# 13-ESP32S3.net
KiCad netlist of a schematic drawn in Altium Designer
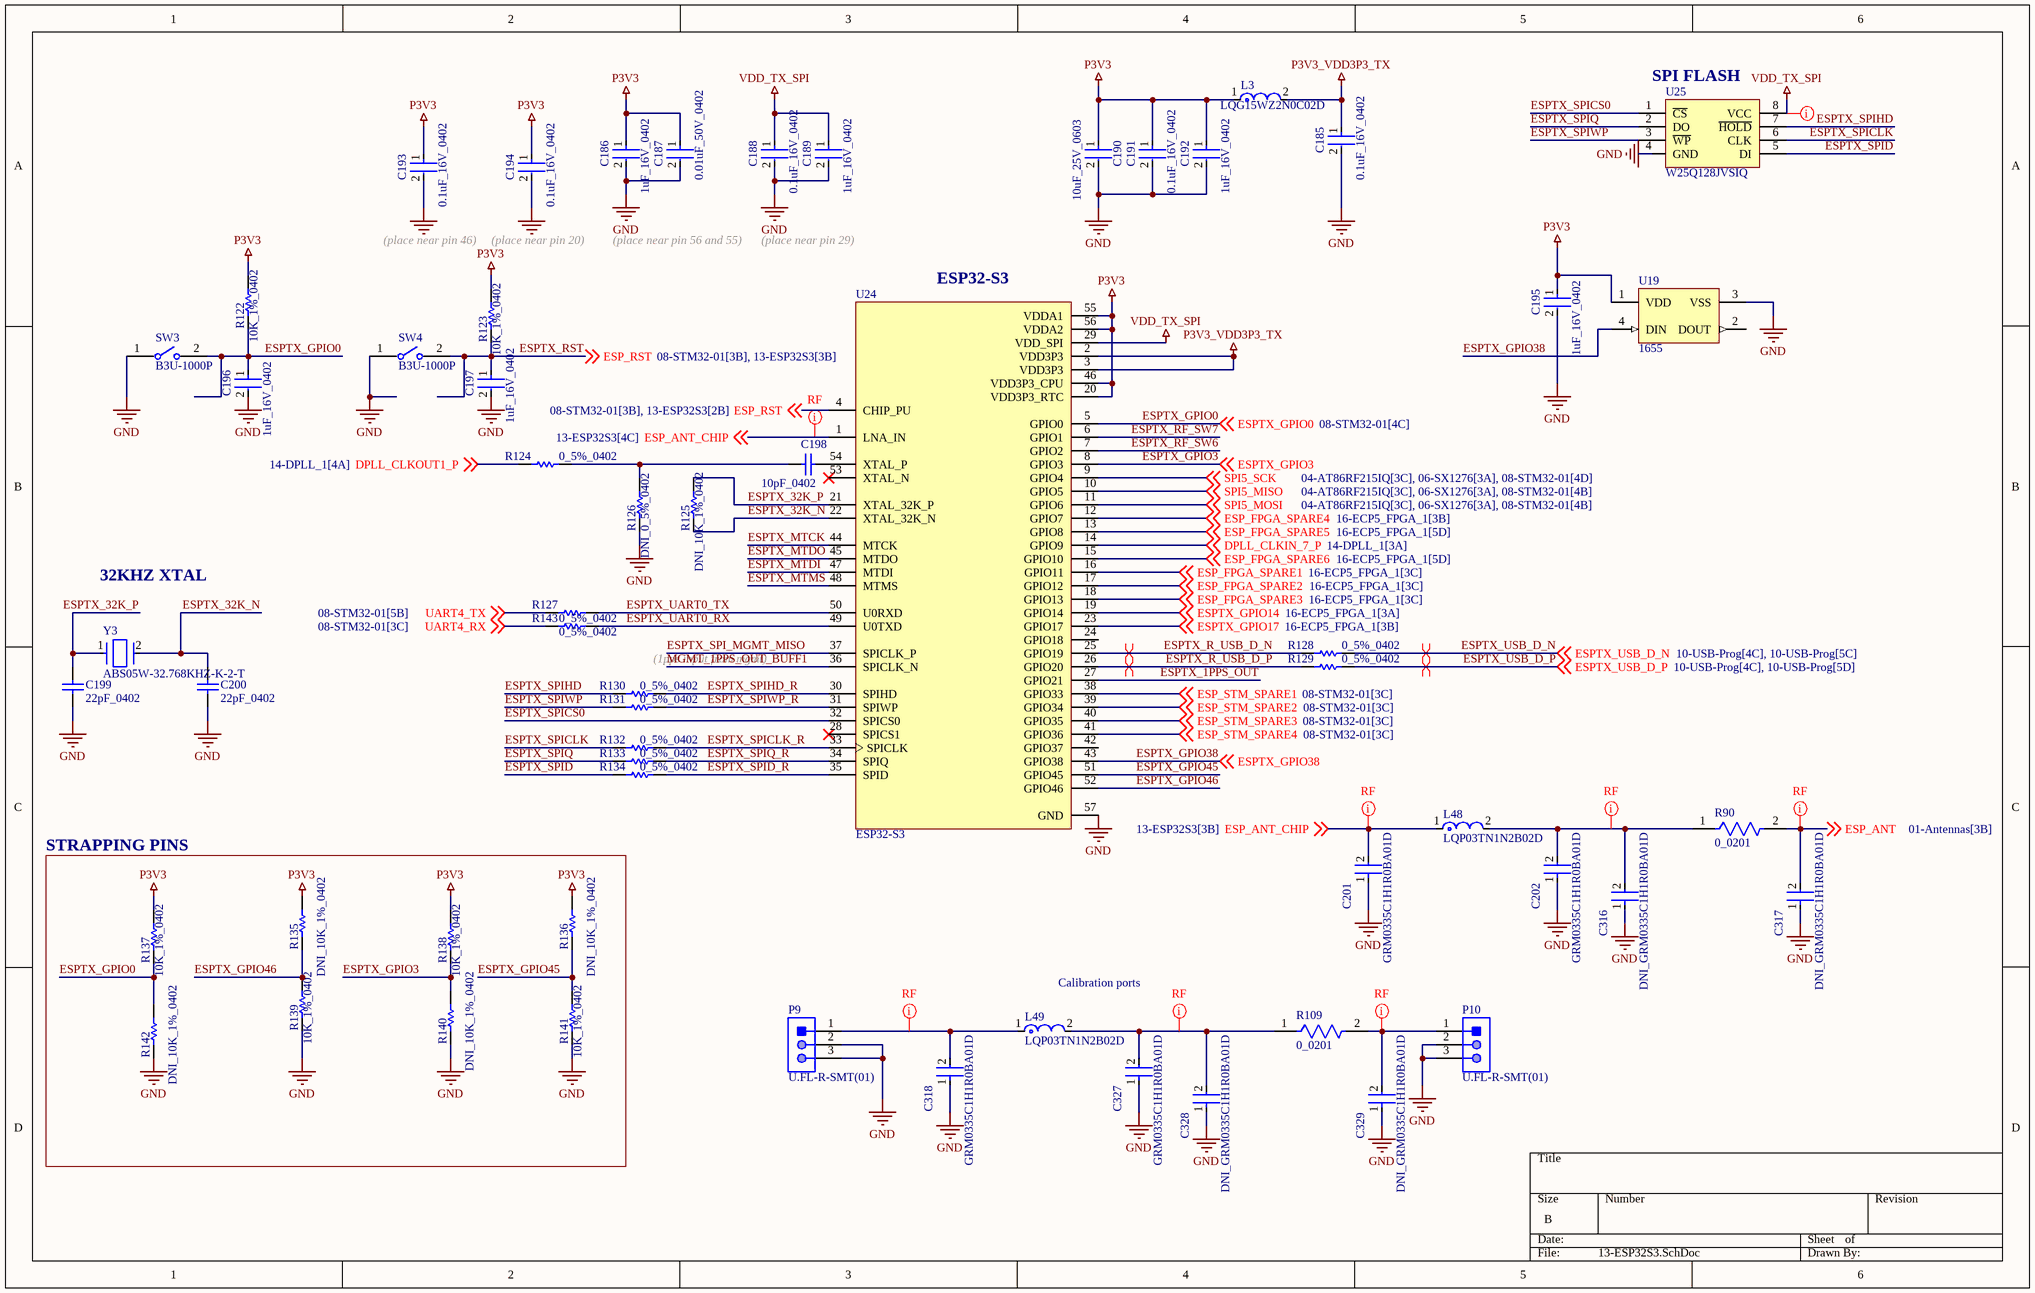
[diagram p0: 13-ESP32S3.SchDoc]

(export (version "E")
  (design (tool "Eeschema 10.0.6"))
  (components
    (comp (ref "C185")
      (value "0.1uF_16V_0402")
      (footprint "FP-C0402-BB-MFG")
      (description "CAP CER 0.1UF 16V 5% X7R 0402")
      (fields
        (field (name "MANUFACTURER") "Kemet")
        (field (name "MANUFACTURER PART NUMBER") "C0402C104J4RACTU")
      )
      (libsource (lib "Altium Content Vault") (part "b4654b650e69147ec39a6b967a45e02"))
    )
    (comp (ref "C186")
      (value "1uF_16V_0402")
      (footprint "FP-0402-L_1_0_0_05-W_0_5-IPC_A")
      (description "None")
      (fields (field (name "TOLERANCE") "10%"))
      (libsource (lib "Altium Content Vault") (part "b4654b650e69147ec39a6b967a45e02"))
    )
    (comp (ref "C187")
      (value "0.01uF_50V_0402")
      (footprint "FP-GCM155-0_05-IPC_C")
      (description "Ceramic Capacitor for Automotive 10nF ±10% 50VDC X7R 0402 Paper T/R")
      (fields (field (name "TOLERANCE") "10%") (field (name "VOLTAGE") "50V"))
      (libsource (lib "Altium Content Vault") (part "02cd4be3c70576c341d710602a673aa"))
    )
    (comp (ref "C188")
      (value "0.1uF_16V_0402")
      (footprint "FP-C0402-BB-MFG")
      (description "CAP CER 0.1UF 16V 5% X7R 0402")
      (fields
        (field (name "MANUFACTURER") "Kemet")
        (field (name "MANUFACTURER PART NUMBER") "C0402C104J4RACTU")
      )
      (libsource (lib "Altium Content Vault") (part "b4654b650e69147ec39a6b967a45e02"))
    )
    (comp (ref "C189")
      (value "1uF_16V_0402")
      (footprint "FP-0402-L_1_0_0_05-W_0_5-IPC_A")
      (description "None")
      (fields (field (name "TOLERANCE") "10%"))
      (libsource (lib "Altium Content Vault") (part "b4654b650e69147ec39a6b967a45e02"))
    )
    (comp (ref "C190")
      (value "10uF_25V_0603")
      (footprint "FP-CL10-IPC_C")
      (description "Cap Ceramic 10uF 25V X5R ±20% Pad SMD 0603 +85°C T/R")
      (fields (field (name "TOLERANCE") "20%"))
      (libsource (lib "Altium Content Vault") (part "b4654b650e69147ec39a6b967a45e02"))
    )
    (comp (ref "C191")
      (value "0.1uF_16V_0402")
      (footprint "FP-C0402-BB-MFG")
      (description "CAP CER 0.1UF 16V 5% X7R 0402")
      (fields
        (field (name "MANUFACTURER") "Kemet")
        (field (name "MANUFACTURER PART NUMBER") "C0402C104J4RACTU")
      )
      (libsource (lib "Altium Content Vault") (part "b4654b650e69147ec39a6b967a45e02"))
    )
    (comp (ref "C192")
      (value "1uF_16V_0402")
      (footprint "FP-0402-L_1_0_0_05-W_0_5-IPC_A")
      (description "None")
      (fields (field (name "TOLERANCE") "10%"))
      (libsource (lib "Altium Content Vault") (part "b4654b650e69147ec39a6b967a45e02"))
    )
    (comp (ref "C193")
      (value "0.1uF_16V_0402")
      (footprint "FP-C0402-BB-MFG")
      (description "CAP CER 0.1UF 16V 5% X7R 0402")
      (fields
        (field (name "MANUFACTURER") "Kemet")
        (field (name "MANUFACTURER PART NUMBER") "C0402C104J4RACTU")
      )
      (libsource (lib "Altium Content Vault") (part "b4654b650e69147ec39a6b967a45e02"))
    )
    (comp (ref "C194")
      (value "0.1uF_16V_0402")
      (footprint "FP-C0402-BB-MFG")
      (description "CAP CER 0.1UF 16V 5% X7R 0402")
      (fields
        (field (name "MANUFACTURER") "Kemet")
        (field (name "MANUFACTURER PART NUMBER") "C0402C104J4RACTU")
      )
      (libsource (lib "Altium Content Vault") (part "b4654b650e69147ec39a6b967a45e02"))
    )
    (comp (ref "C195")
      (value "1uF_16V_0402")
      (footprint "FP-0402-L_1_0_0_05-W_0_5-IPC_A")
      (description "None")
      (fields (field (name "TOLERANCE") "10%"))
      (libsource (lib "Altium Content Vault") (part "b4654b650e69147ec39a6b967a45e02"))
    )
    (comp (ref "C196")
      (value "1uF_16V_0402")
      (footprint "FP-0402-L_1_0_0_05-W_0_5-IPC_A")
      (description "None")
      (fields (field (name "TOLERANCE") "10%"))
      (libsource (lib "Altium Content Vault") (part "b4654b650e69147ec39a6b967a45e02"))
    )
    (comp (ref "C197")
      (value "1uF_16V_0402")
      (footprint "FP-0402-L_1_0_0_05-W_0_5-IPC_A")
      (description "None")
      (fields (field (name "TOLERANCE") "10%"))
      (libsource (lib "Altium Content Vault") (part "b4654b650e69147ec39a6b967a45e02"))
    )
    (comp (ref "C198")
      (value "10pF_0402")
      (footprint "CAPC1005X55X25ML05T05")
      (description "Chip Capacitor, 10 pF, +/- 5%, 50 V, -55 to 125 degC, 0402 (1005 Metric), RoHS, Tape and Reel")
      (fields (field (name "TOLERANCE") "5%") (field (name "MANUFACTURER") "Yageo"))
      (libsource (lib "Altium Content Vault") (part "CAP-NP-2"))
    )
    (comp (ref "C199")
      (value "22pF_0402")
      (footprint "CAPC1005X55X25ML05T05")
      (description "Chip Capacitor, 22 pF, +/- 5%, 50 V, -55 to 125 degC, 0402 (1005 Metric), RoHS, Tape and Reel")
      (fields (field (name "MANUFACTURER") "Yageo") (field (name "TOLERANCE") "5%"))
      (libsource (lib "Altium Content Vault") (part "CAP-NP-2"))
    )
    (comp (ref "C200")
      (value "22pF_0402")
      (footprint "CAPC1005X55X25ML05T05")
      (description "Chip Capacitor, 22 pF, +/- 5%, 50 V, -55 to 125 degC, 0402 (1005 Metric), RoHS, Tape and Reel")
      (fields (field (name "MANUFACTURER") "Yageo") (field (name "TOLERANCE") "5%"))
      (libsource (lib "Altium Content Vault") (part "CAP-NP-2"))
    )
    (comp (ref "C201")
      (value "GRM0335C1H1R0BA01D")
      (footprint "FP-GRM033-0_03-IPC_C")
      (description "Chip Multilayer Ceramic Capacitors for General Purpose, 0201, 1.0pF, C0G, 30ppm/°C, 0.1pF, 50V")
      (libsource (lib "Altium Content Vault") (part "b4654b650e69147ec39a6b967a45e02"))
    )
    (comp (ref "C202")
      (value "GRM0335C1H1R0BA01D")
      (footprint "FP-GRM033-0_03-IPC_C")
      (description "Chip Multilayer Ceramic Capacitors for General Purpose, 0201, 1.0pF, C0G, 30ppm/°C, 0.1pF, 50V")
      (libsource (lib "Altium Content Vault") (part "b4654b650e69147ec39a6b967a45e02"))
    )
    (comp (ref "C316")
      (value "DNI_GRM0335C1H1R0BA01D")
      (footprint "FP-GRM033-0_03-IPC_C")
      (description "Chip Multilayer Ceramic Capacitors for General Purpose, 0201, 1.0pF, C0G, 30ppm/°C, 0.1pF, 50V")
      (libsource (lib "Altium Content Vault") (part "b4654b650e69147ec39a6b967a45e02"))
    )
    (comp (ref "C317")
      (value "DNI_GRM0335C1H1R0BA01D")
      (footprint "FP-GRM033-0_03-IPC_C")
      (description "Chip Multilayer Ceramic Capacitors for General Purpose, 0201, 1.0pF, C0G, 30ppm/°C, 0.1pF, 50V")
      (libsource (lib "Altium Content Vault") (part "b4654b650e69147ec39a6b967a45e02"))
    )
    (comp (ref "C318")
      (value "GRM0335C1H1R0BA01D")
      (footprint "FP-GRM033-0_03-IPC_C")
      (description "Chip Multilayer Ceramic Capacitors for General Purpose, 0201, 1.0pF, C0G, 30ppm/°C, 0.1pF, 50V")
      (libsource (lib "Altium Content Vault") (part "b4654b650e69147ec39a6b967a45e02"))
    )
    (comp (ref "C327")
      (value "GRM0335C1H1R0BA01D")
      (footprint "FP-GRM033-0_03-IPC_C")
      (description "Chip Multilayer Ceramic Capacitors for General Purpose, 0201, 1.0pF, C0G, 30ppm/°C, 0.1pF, 50V")
      (libsource (lib "Altium Content Vault") (part "b4654b650e69147ec39a6b967a45e02"))
    )
    (comp (ref "C328")
      (value "DNI_GRM0335C1H1R0BA01D")
      (footprint "FP-GRM033-0_03-IPC_C")
      (description "Chip Multilayer Ceramic Capacitors for General Purpose, 0201, 1.0pF, C0G, 30ppm/°C, 0.1pF, 50V")
      (libsource (lib "Altium Content Vault") (part "b4654b650e69147ec39a6b967a45e02"))
    )
    (comp (ref "C329")
      (value "DNI_GRM0335C1H1R0BA01D")
      (footprint "FP-GRM033-0_03-IPC_C")
      (description "Chip Multilayer Ceramic Capacitors for General Purpose, 0201, 1.0pF, C0G, 30ppm/°C, 0.1pF, 50V")
      (libsource (lib "Altium Content Vault") (part "b4654b650e69147ec39a6b967a45e02"))
    )
    (comp (ref "L3")
      (value "LQG15WZ2N0C02D")
      (footprint "FP-LQG15WH_02-IPC_B")
      (description "Multilayer type Inductor for Automotive 2nH ±0.2nH 0.05Ω 1000mA 0402")
      (libsource (lib "Altium Content Vault") (part "4cc4b267dca4c8e51f7102f422741d8"))
    )
    (comp (ref "L48")
      (value "LQP03TN1N2B02D")
      (footprint "FP-LQP03TG_02-IPC_A")
      (description "Film type RF Inductor 1.2nH ±0.1nH 750mA 0.1Ω 0201 (0603)")
      (libsource (lib "Altium Content Vault") (part "4cc4b267dca4c8e51f7102f422741d8"))
    )
    (comp (ref "L49")
      (value "LQP03TN1N2B02D")
      (footprint "FP-LQP03TG_02-IPC_A")
      (description "Film type RF Inductor 1.2nH ±0.1nH 750mA 0.1Ω 0201 (0603)")
      (libsource (lib "Altium Content Vault") (part "4cc4b267dca4c8e51f7102f422741d8"))
    )
    (comp (ref "P9")
      (value "U.FL-R-SMT(01)")
      (footprint "HRS-U.FL-R-SMT(10)_V")
      (description "CONN RECPT ULTRA-MINI COAX SMD")
      (fields (field (name "MANUFACTURER") "Hirose Electric") (field (name "APPROVAL CATEGORY") "UL94V-0"))
      (libsource (lib "") (part "CN-1P-M-R3_1"))
    )
    (comp (ref "P10")
      (value "U.FL-R-SMT(01)")
      (footprint "HRS-U.FL-R-SMT(10)_V")
      (description "CONN RECPT ULTRA-MINI COAX SMD")
      (fields (field (name "MANUFACTURER") "Hirose Electric") (field (name "APPROVAL CATEGORY") "UL94V-0"))
      (libsource (lib "Altium Content Vault") (part "CN-1P-M-R3"))
    )
    (comp (ref "R90")
      (value "0_0201")
      (footprint "FP-RC_L0201-MFG")
      (description "RES SMD 0 OHM JUMPER 1/20W 0201")
      (fields
        (field (name "OCTOPART") "https://octopart.com/rc0201jr-070rl-yageo-43171986")
        (field (name "MANUFACTURER") "Yageo")
      )
      (libsource (lib "Altium Content Vault") (part "1029c3af85768c4190bb7ad29bc67b5"))
    )
    (comp (ref "R109")
      (value "0_0201")
      (footprint "FP-RC_L0201-MFG")
      (description "RES SMD 0 OHM JUMPER 1/20W 0201")
      (fields
        (field (name "OCTOPART") "https://octopart.com/rc0201jr-070rl-yageo-43171986")
        (field (name "MANUFACTURER") "Yageo")
      )
      (libsource (lib "Altium Content Vault") (part "1029c3af85768c4190bb7ad29bc67b5"))
    )
    (comp (ref "R122")
      (value "10K_1%_0402")
      (footprint "RESC1005X40X25NL10T10")
      (fields (field (name "MANUFACTURER") "Bourns") (field (name "PART NUMBER") "CR0402-FX-1002GLF"))
      (libsource (lib "Altium Content Vault") (part "RES"))
    )
    (comp (ref "R123")
      (value "10K_1%_0402")
      (footprint "RESC1005X40X25NL10T10")
      (fields (field (name "MANUFACTURER") "Bourns") (field (name "PART NUMBER") "CR0402-FX-1002GLF"))
      (libsource (lib "Altium Content Vault") (part "RES"))
    )
    (comp (ref "R124")
      (value "0_5%_0402")
      (footprint "RESC1005X40X25NL05T10")
      (fields (field (name "MANUFACTURER") "Panasonic") (field (name "PART NUMBER") "ERJ-U020R00X"))
      (libsource (lib "Altium Content Vault") (part "RES"))
    )
    (comp (ref "R125")
      (value "DNI_10K_1%_0402")
      (footprint "RESC1005X40X25NL10T10")
      (fields (field (name "MANUFACTURER") "Bourns") (field (name "PART NUMBER") "CR0402-FX-1002GLF"))
      (libsource (lib "Altium Content Vault") (part "RES"))
    )
    (comp (ref "R126")
      (value "DNI_0_5%_0402")
      (footprint "RESC1005X40X25NL05T10")
      (fields (field (name "MANUFACTURER") "Panasonic") (field (name "PART NUMBER") "ERJ-U020R00X"))
      (libsource (lib "Altium Content Vault") (part "RES"))
    )
    (comp (ref "R127")
      (value "0_5%_0402")
      (footprint "RESC1005X40X25NL05T10")
      (fields (field (name "MANUFACTURER") "Panasonic") (field (name "PART NUMBER") "ERJ-U020R00X"))
      (libsource (lib "Altium Content Vault") (part "RES"))
    )
    (comp (ref "R128")
      (value "0_5%_0402")
      (footprint "RESC1005X40X25NL05T10")
      (fields (field (name "MANUFACTURER") "Panasonic") (field (name "PART NUMBER") "ERJ-U020R00X"))
      (libsource (lib "Altium Content Vault") (part "RES"))
    )
    (comp (ref "R129")
      (value "0_5%_0402")
      (footprint "RESC1005X40X25NL05T10")
      (fields (field (name "MANUFACTURER") "Panasonic") (field (name "PART NUMBER") "ERJ-U020R00X"))
      (libsource (lib "Altium Content Vault") (part "RES"))
    )
    (comp (ref "R130")
      (value "0_5%_0402")
      (footprint "RESC1005X40X25NL05T10")
      (fields (field (name "MANUFACTURER") "Panasonic") (field (name "PART NUMBER") "ERJ-U020R00X"))
      (libsource (lib "Altium Content Vault") (part "RES"))
    )
    (comp (ref "R131")
      (value "0_5%_0402")
      (footprint "RESC1005X40X25NL05T10")
      (fields (field (name "MANUFACTURER") "Panasonic") (field (name "PART NUMBER") "ERJ-U020R00X"))
      (libsource (lib "Altium Content Vault") (part "RES"))
    )
    (comp (ref "R132")
      (value "0_5%_0402")
      (footprint "RESC1005X40X25NL05T10")
      (fields (field (name "MANUFACTURER") "Panasonic") (field (name "PART NUMBER") "ERJ-U020R00X"))
      (libsource (lib "Altium Content Vault") (part "RES"))
    )
    (comp (ref "R133")
      (value "0_5%_0402")
      (footprint "RESC1005X40X25NL05T10")
      (fields (field (name "MANUFACTURER") "Panasonic") (field (name "PART NUMBER") "ERJ-U020R00X"))
      (libsource (lib "Altium Content Vault") (part "RES"))
    )
    (comp (ref "R134")
      (value "0_5%_0402")
      (footprint "RESC1005X40X25NL05T10")
      (fields (field (name "MANUFACTURER") "Panasonic") (field (name "PART NUMBER") "ERJ-U020R00X"))
      (libsource (lib "Altium Content Vault") (part "RES"))
    )
    (comp (ref "R135")
      (value "DNI_10K_1%_0402")
      (footprint "RESC1005X40X25NL10T10")
      (fields (field (name "MANUFACTURER") "Bourns") (field (name "PART NUMBER") "CR0402-FX-1002GLF"))
      (libsource (lib "Altium Content Vault") (part "RES"))
    )
    (comp (ref "R136")
      (value "DNI_10K_1%_0402")
      (footprint "RESC1005X40X25NL10T10")
      (fields (field (name "MANUFACTURER") "Bourns") (field (name "PART NUMBER") "CR0402-FX-1002GLF"))
      (libsource (lib "Altium Content Vault") (part "RES"))
    )
    (comp (ref "R137")
      (value "10K_1%_0402")
      (footprint "RESC1005X40X25NL10T10")
      (fields (field (name "MANUFACTURER") "Bourns") (field (name "PART NUMBER") "CR0402-FX-1002GLF"))
      (libsource (lib "Altium Content Vault") (part "RES"))
    )
    (comp (ref "R138")
      (value "10K_1%_0402")
      (footprint "RESC1005X40X25NL10T10")
      (fields (field (name "MANUFACTURER") "Bourns") (field (name "PART NUMBER") "CR0402-FX-1002GLF"))
      (libsource (lib "Altium Content Vault") (part "RES"))
    )
    (comp (ref "R139")
      (value "10K_1%_0402")
      (footprint "RESC1005X40X25NL10T10")
      (fields (field (name "MANUFACTURER") "Bourns") (field (name "PART NUMBER") "CR0402-FX-1002GLF"))
      (libsource (lib "Altium Content Vault") (part "RES"))
    )
    (comp (ref "R140")
      (value "DNI_10K_1%_0402")
      (footprint "RESC1005X40X25NL10T10")
      (fields (field (name "MANUFACTURER") "Bourns") (field (name "PART NUMBER") "CR0402-FX-1002GLF"))
      (libsource (lib "Altium Content Vault") (part "RES"))
    )
    (comp (ref "R141")
      (value "10K_1%_0402")
      (footprint "RESC1005X40X25NL10T10")
      (fields (field (name "MANUFACTURER") "Bourns") (field (name "PART NUMBER") "CR0402-FX-1002GLF"))
      (libsource (lib "Altium Content Vault") (part "RES"))
    )
    (comp (ref "R142")
      (value "DNI_10K_1%_0402")
      (footprint "RESC1005X40X25NL10T10")
      (fields (field (name "MANUFACTURER") "Bourns") (field (name "PART NUMBER") "CR0402-FX-1002GLF"))
      (libsource (lib "Altium Content Vault") (part "RES"))
    )
    (comp (ref "R143")
      (value "0_5%_0402")
      (footprint "RESC1005X40X25NL05T10")
      (fields (field (name "MANUFACTURER") "Panasonic") (field (name "PART NUMBER") "ERJ-U020R00X"))
      (libsource (lib "Altium Content Vault") (part "RES"))
    )
    (comp (ref "SW3")
      (value "B3U-1000P")
      (footprint "FP-B3U-1000P-MFG")
      (description "SWITCH TACTILE SPST-NO 0.05A 12V")
      (libsource (lib "Altium Content Vault") (part "ae622034201233ca1abcedc05908f33"))
    )
    (comp (ref "SW4")
      (value "B3U-1000P")
      (footprint "FP-B3U-1000P-MFG")
      (description "SWITCH TACTILE SPST-NO 0.05A 12V")
      (libsource (lib "Altium Content Vault") (part "ae622034201233ca1abcedc05908f33"))
    )
    (comp (ref "U19")
      (value "1655")
      (footprint "ADA-RGB-1655_V")
      (fields (field (name "MANUFACTURER") "Adafruit-Industries-LLC"))
      (libsource (lib "Altium Content Vault") (part "ADA-RGB-1655-4"))
    )
    (comp (ref "U24")
      (value "ESP32-S3")
      (footprint "IC_ESP32-S3")
      (fields (field (name "MF") "Espressif Systems"))
      (libsource (lib "LotusSound") (part "IC_ESP32-S3"))
    )
    (comp (ref "U25")
      (value "W25Q128JVSIQ")
      (footprint "IC_W25Q128JVSIQ")
      (description "NOR Flash Serial (SPI, Dual SPI, Quad SPI) 3.3V 128M-bit 16M x 8 6ns 8-Pin SOIC Tube")
      (fields (field (name "MANUFACTURER") "Winbond"))
      (libsource (lib "LotusSound") (part "IC_W25Q128JVSIQ"))
    )
    (comp (ref "Y3")
      (value "ABS05W-32.768KHZ-K-2-T")
      (footprint "FP-ABS05W-MFG")
      (description "Crystal 32.768kHz ±20ppm (Tol) 4pF 85kΩ 2-Pin SMD T/R")
      (libsource (lib "Altium Content Vault") (part "c23a69dc6c9e2f18f2079038eb95dd1"))
    )
  )
  (nets
    (net (code "1") (name "/ESPTX_1PPS_OUT") (class "Default")
      (node (ref "U24") (pin "27") (pinfunction "GPIO21_27") (pintype "passive"))
    )
    (net (code "2") (name "/ESPTX_32K_N") (class "Default")
      (node (ref "C200") (pin "2") (pinfunction "2_2") (pintype "passive"))
      (node (ref "R125") (pin "1") (pinfunction "1_1") (pintype "passive"))
      (node (ref "U24") (pin "22") (pinfunction "XTAL_32K_N_22") (pintype "passive"))
      (node (ref "Y3") (pin "2") (pinfunction "2_2") (pintype "passive"))
    )
    (net (code "3") (name "/ESPTX_32K_P") (class "Default")
      (node (ref "C199") (pin "2") (pinfunction "2_2") (pintype "passive"))
      (node (ref "R125") (pin "2") (pinfunction "2_2") (pintype "passive"))
      (node (ref "U24") (pin "21") (pinfunction "XTAL_32K_P_21") (pintype "passive"))
      (node (ref "Y3") (pin "1") (pinfunction "1_1") (pintype "passive"))
    )
    (net (code "4") (name "/ESPTX_GPIO45") (class "Default")
      (node (ref "R136") (pin "1") (pinfunction "1_1") (pintype "passive"))
      (node (ref "R141") (pin "2") (pinfunction "2_2") (pintype "passive"))
      (node (ref "U24") (pin "51") (pinfunction "GPIO45_51") (pintype "passive"))
    )
    (net (code "5") (name "/ESPTX_GPIO46") (class "Default")
      (node (ref "R135") (pin "1") (pinfunction "1_1") (pintype "passive"))
      (node (ref "R139") (pin "2") (pinfunction "2_2") (pintype "passive"))
      (node (ref "U24") (pin "52") (pinfunction "GPIO46_52") (pintype "passive"))
    )
    (net (code "6") (name "/ESPTX_MTCK") (class "Default")
      (node (ref "U24") (pin "44") (pinfunction "MTCK_44") (pintype "passive"))
    )
    (net (code "7") (name "/ESPTX_MTDI") (class "Default")
      (node (ref "U24") (pin "47") (pinfunction "MTDI_47") (pintype "passive"))
    )
    (net (code "8") (name "/ESPTX_MTDO") (class "Default")
      (node (ref "U24") (pin "45") (pinfunction "MTDO_45") (pintype "passive"))
    )
    (net (code "9") (name "/ESPTX_MTMS") (class "Default")
      (node (ref "U24") (pin "48") (pinfunction "MTMS_48") (pintype "passive"))
    )
    (net (code "10") (name "/ESPTX_RF_SW6") (class "Default")
      (node (ref "U24") (pin "7") (pinfunction "GPIO2_7") (pintype "passive"))
    )
    (net (code "11") (name "/ESPTX_RF_SW7") (class "Default")
      (node (ref "U24") (pin "6") (pinfunction "GPIO1_6") (pintype "passive"))
    )
    (net (code "12") (name "/ESPTX_R_USB_D_N") (class "Default")
      (node (ref "R128") (pin "1") (pinfunction "1_1") (pintype "passive"))
      (node (ref "U24") (pin "25") (pinfunction "GPIO19_25") (pintype "passive"))
    )
    (net (code "13") (name "/ESPTX_R_USB_D_P") (class "Default")
      (node (ref "R129") (pin "1") (pinfunction "1_1") (pintype "passive"))
      (node (ref "U24") (pin "26") (pinfunction "GPIO20_26") (pintype "passive"))
    )
    (net (code "14") (name "/ESPTX_SPICLK") (class "Default")
      (node (ref "R132") (pin "1") (pinfunction "1_1") (pintype "passive"))
      (node (ref "U25") (pin "6") (pinfunction "CLK_6") (pintype "passive"))
    )
    (net (code "15") (name "/ESPTX_SPICLK_R") (class "Default")
      (node (ref "R132") (pin "2") (pinfunction "2_2") (pintype "passive"))
      (node (ref "U24") (pin "33") (pinfunction "SPICLK_33") (pintype "passive"))
    )
    (net (code "16") (name "/ESPTX_SPICS0") (class "Default")
      (node (ref "U24") (pin "32") (pinfunction "SPICS0_32") (pintype "passive"))
      (node (ref "U25") (pin "1") (pinfunction "~{CS}_1") (pintype "passive"))
    )
    (net (code "17") (name "/ESPTX_SPID") (class "Default")
      (node (ref "R134") (pin "1") (pinfunction "1_1") (pintype "passive"))
      (node (ref "U25") (pin "5") (pinfunction "DI_5") (pintype "passive"))
    )
    (net (code "18") (name "/ESPTX_SPID_R") (class "Default")
      (node (ref "R134") (pin "2") (pinfunction "2_2") (pintype "passive"))
      (node (ref "U24") (pin "35") (pinfunction "SPID_35") (pintype "passive"))
    )
    (net (code "19") (name "/ESPTX_SPIHD") (class "Default")
      (node (ref "R130") (pin "1") (pinfunction "1_1") (pintype "passive"))
      (node (ref "U25") (pin "7") (pinfunction "~{HOLD}_7") (pintype "passive"))
    )
    (net (code "20") (name "/ESPTX_SPIHD_R") (class "Default")
      (node (ref "R130") (pin "2") (pinfunction "2_2") (pintype "passive"))
      (node (ref "U24") (pin "30") (pinfunction "SPIHD_30") (pintype "passive"))
    )
    (net (code "21") (name "/ESPTX_SPIQ") (class "Default")
      (node (ref "R133") (pin "1") (pinfunction "1_1") (pintype "passive"))
      (node (ref "U25") (pin "2") (pinfunction "DO_2") (pintype "passive"))
    )
    (net (code "22") (name "/ESPTX_SPIQ_R") (class "Default")
      (node (ref "R133") (pin "2") (pinfunction "2_2") (pintype "passive"))
      (node (ref "U24") (pin "34") (pinfunction "SPIQ_34") (pintype "passive"))
    )
    (net (code "23") (name "/ESPTX_SPIWP") (class "Default")
      (node (ref "R131") (pin "1") (pinfunction "1_1") (pintype "passive"))
      (node (ref "U25") (pin "3") (pinfunction "~{WP}_3") (pintype "passive"))
    )
    (net (code "24") (name "/ESPTX_SPIWP_R") (class "Default")
      (node (ref "R131") (pin "2") (pinfunction "2_2") (pintype "passive"))
      (node (ref "U24") (pin "31") (pinfunction "SPIWP_31") (pintype "passive"))
    )
    (net (code "25") (name "/ESPTX_SPI_MGMT_MISO") (class "Default")
      (node (ref "U24") (pin "37") (pinfunction "SPICLK_P_37") (pintype "passive"))
    )
    (net (code "26") (name "/ESPTX_UART0_RX") (class "Default")
      (node (ref "R143") (pin "2") (pinfunction "2_2") (pintype "passive"))
      (node (ref "U24") (pin "49") (pinfunction "U0TXD_49") (pintype "passive"))
    )
    (net (code "27") (name "/ESPTX_UART0_TX") (class "Default")
      (node (ref "R127") (pin "2") (pinfunction "2_2") (pintype "passive"))
      (node (ref "U24") (pin "50") (pinfunction "U0RXD_50") (pintype "passive"))
    )
    (net (code "28") (name "/MGMT_1PPS_OUT_BUFF1") (class "Default")
      (node (ref "U24") (pin "36") (pinfunction "SPICLK_N_36") (pintype "passive"))
    )
    (net (code "29") (name "DPLL_CLKIN_7_P") (class "Default")
      (node (ref "U24") (pin "14") (pinfunction "GPIO9_14") (pintype "passive"))
    )
    (net (code "30") (name "DPLL_CLKOUT1_P") (class "Default")
      (node (ref "R124") (pin "1") (pinfunction "1_1") (pintype "passive"))
    )
    (net (code "31") (name "ESPTX_GPIO0") (class "Default")
      (node (ref "C196") (pin "1") (pinfunction "1_1") (pintype "passive"))
      (node (ref "R122") (pin "1") (pinfunction "1_1") (pintype "passive"))
      (node (ref "R137") (pin "1") (pinfunction "1_1") (pintype "passive"))
      (node (ref "R142") (pin "2") (pinfunction "2_2") (pintype "passive"))
      (node (ref "SW3") (pin "2") (pinfunction "2_2") (pintype "passive"))
      (node (ref "U24") (pin "5") (pinfunction "GPIO0_5") (pintype "passive"))
    )
    (net (code "32") (name "ESPTX_GPIO3") (class "Default")
      (node (ref "R138") (pin "1") (pinfunction "1_1") (pintype "passive"))
      (node (ref "R140") (pin "2") (pinfunction "2_2") (pintype "passive"))
      (node (ref "U24") (pin "8") (pinfunction "GPIO3_8") (pintype "passive"))
    )
    (net (code "33") (name "ESPTX_GPIO14") (class "Default")
      (node (ref "U24") (pin "19") (pinfunction "GPIO14_19") (pintype "passive"))
    )
    (net (code "34") (name "ESPTX_GPIO17") (class "Default")
      (node (ref "U24") (pin "23") (pinfunction "GPIO17_23") (pintype "passive"))
    )
    (net (code "35") (name "ESPTX_GPIO38") (class "Default")
      (node (ref "U19") (pin "4") (pinfunction "DIN_4") (pintype "input"))
      (node (ref "U24") (pin "43") (pinfunction "GPIO38_43") (pintype "passive"))
    )
    (net (code "36") (name "ESPTX_USB_D_N") (class "Default")
      (node (ref "R128") (pin "2") (pinfunction "2_2") (pintype "passive"))
    )
    (net (code "37") (name "ESPTX_USB_D_P") (class "Default")
      (node (ref "R129") (pin "2") (pinfunction "2_2") (pintype "passive"))
    )
    (net (code "38") (name "ESP_ANT") (class "Default")
      (node (ref "C317") (pin "2") (pinfunction "2_2") (pintype "passive"))
      (node (ref "R90") (pin "2") (pinfunction "2_2") (pintype "passive"))
    )
    (net (code "39") (name "ESP_ANT_CHIP") (class "Default")
      (node (ref "C201") (pin "2") (pinfunction "2_2") (pintype "passive"))
      (node (ref "L48") (pin "1") (pinfunction "1_1") (pintype "passive"))
      (node (ref "U24") (pin "1") (pinfunction "LNA_IN_1") (pintype "passive"))
    )
    (net (code "40") (name "ESP_FPGA_SPARE1") (class "Default")
      (node (ref "U24") (pin "16") (pinfunction "GPIO11_16") (pintype "passive"))
    )
    (net (code "41") (name "ESP_FPGA_SPARE2") (class "Default")
      (node (ref "U24") (pin "17") (pinfunction "GPIO12_17") (pintype "passive"))
    )
    (net (code "42") (name "ESP_FPGA_SPARE3") (class "Default")
      (node (ref "U24") (pin "18") (pinfunction "GPIO13_18") (pintype "passive"))
    )
    (net (code "43") (name "ESP_FPGA_SPARE4") (class "Default")
      (node (ref "U24") (pin "12") (pinfunction "GPIO7_12") (pintype "passive"))
    )
    (net (code "44") (name "ESP_FPGA_SPARE5") (class "Default")
      (node (ref "U24") (pin "13") (pinfunction "GPIO8_13") (pintype "passive"))
    )
    (net (code "45") (name "ESP_FPGA_SPARE6") (class "Default")
      (node (ref "U24") (pin "15") (pinfunction "GPIO10_15") (pintype "passive"))
    )
    (net (code "46") (name "ESP_RST") (class "Default")
      (node (ref "C197") (pin "1") (pinfunction "1_1") (pintype "passive"))
      (node (ref "R123") (pin "1") (pinfunction "1_1") (pintype "passive"))
      (node (ref "SW4") (pin "2") (pinfunction "2_2") (pintype "passive"))
      (node (ref "U24") (pin "4") (pinfunction "CHIP_PU_4") (pintype "passive"))
    )
    (net (code "47") (name "ESP_STM_SPARE1") (class "Default")
      (node (ref "U24") (pin "38") (pinfunction "GPIO33_38") (pintype "passive"))
    )
    (net (code "48") (name "ESP_STM_SPARE2") (class "Default")
      (node (ref "U24") (pin "39") (pinfunction "GPIO34_39") (pintype "passive"))
    )
    (net (code "49") (name "ESP_STM_SPARE3") (class "Default")
      (node (ref "U24") (pin "40") (pinfunction "GPIO35_40") (pintype "passive"))
    )
    (net (code "50") (name "ESP_STM_SPARE4") (class "Default")
      (node (ref "U24") (pin "41") (pinfunction "GPIO36_41") (pintype "passive"))
    )
    (net (code "51") (name "GND") (class "Default")
      (node (ref "C185") (pin "2") (pinfunction "2_2") (pintype "passive"))
      (node (ref "C186") (pin "2") (pinfunction "2_2") (pintype "passive"))
      (node (ref "C187") (pin "2") (pinfunction "2_2") (pintype "passive"))
      (node (ref "C188") (pin "2") (pinfunction "2_2") (pintype "passive"))
      (node (ref "C189") (pin "2") (pinfunction "2_2") (pintype "passive"))
      (node (ref "C190") (pin "2") (pinfunction "2_2") (pintype "passive"))
      (node (ref "C191") (pin "2") (pinfunction "2_2") (pintype "passive"))
      (node (ref "C192") (pin "2") (pinfunction "2_2") (pintype "passive"))
      (node (ref "C193") (pin "2") (pinfunction "2_2") (pintype "passive"))
      (node (ref "C194") (pin "2") (pinfunction "2_2") (pintype "passive"))
      (node (ref "C195") (pin "2") (pinfunction "2_2") (pintype "passive"))
      (node (ref "C196") (pin "2") (pinfunction "2_2") (pintype "passive"))
      (node (ref "C197") (pin "2") (pinfunction "2_2") (pintype "passive"))
      (node (ref "C199") (pin "1") (pinfunction "1_1") (pintype "passive"))
      (node (ref "C200") (pin "1") (pinfunction "1_1") (pintype "passive"))
      (node (ref "C201") (pin "1") (pinfunction "1_1") (pintype "passive"))
      (node (ref "C202") (pin "1") (pinfunction "1_1") (pintype "passive"))
      (node (ref "C316") (pin "1") (pinfunction "1_1") (pintype "passive"))
      (node (ref "C317") (pin "1") (pinfunction "1_1") (pintype "passive"))
      (node (ref "C318") (pin "1") (pinfunction "1_1") (pintype "passive"))
      (node (ref "C327") (pin "1") (pinfunction "1_1") (pintype "passive"))
      (node (ref "C328") (pin "1") (pinfunction "1_1") (pintype "passive"))
      (node (ref "C329") (pin "1") (pinfunction "1_1") (pintype "passive"))
      (node (ref "P10") (pin "2") (pinfunction "2_2") (pintype "passive"))
      (node (ref "P10") (pin "3") (pinfunction "3_3") (pintype "passive"))
      (node (ref "P9") (pin "2") (pinfunction "2_2") (pintype "passive"))
      (node (ref "P9") (pin "3") (pinfunction "3_3") (pintype "passive"))
      (node (ref "R126") (pin "1") (pinfunction "1_1") (pintype "passive"))
      (node (ref "R139") (pin "1") (pinfunction "1_1") (pintype "passive"))
      (node (ref "R140") (pin "1") (pinfunction "1_1") (pintype "passive"))
      (node (ref "R141") (pin "1") (pinfunction "1_1") (pintype "passive"))
      (node (ref "R142") (pin "1") (pinfunction "1_1") (pintype "passive"))
      (node (ref "SW3") (pin "1") (pinfunction "1_1") (pintype "passive"))
      (node (ref "SW4") (pin "1") (pinfunction "1_1") (pintype "passive"))
      (node (ref "U19") (pin "3") (pinfunction "VSS_3") (pintype "power_in"))
      (node (ref "U24") (pin "57") (pinfunction "GND_57") (pintype "passive"))
      (node (ref "U25") (pin "4") (pinfunction "GND_4") (pintype "power_in"))
    )
    (net (code "52") (name "Net-(C198-Pad1)") (class "Default")
      (node (ref "C198") (pin "1") (pinfunction "1_1") (pintype "passive"))
      (node (ref "R124") (pin "2") (pinfunction "2_2") (pintype "passive"))
      (node (ref "R126") (pin "2") (pinfunction "2_2") (pintype "passive"))
    )
    (net (code "53") (name "Net-(C202-Pad2)") (class "Default")
      (node (ref "C202") (pin "2") (pinfunction "2_2") (pintype "passive"))
      (node (ref "C316") (pin "2") (pinfunction "2_2") (pintype "passive"))
      (node (ref "L48") (pin "2") (pinfunction "2_2") (pintype "passive"))
      (node (ref "R90") (pin "1") (pinfunction "1_1") (pintype "passive"))
    )
    (net (code "54") (name "Net-(C318-Pad2)") (class "Default")
      (node (ref "C318") (pin "2") (pinfunction "2_2") (pintype "passive"))
      (node (ref "L49") (pin "1") (pinfunction "1_1") (pintype "passive"))
      (node (ref "P9") (pin "1") (pinfunction "1_1") (pintype "passive"))
    )
    (net (code "55") (name "Net-(C327-Pad2)") (class "Default")
      (node (ref "C327") (pin "2") (pinfunction "2_2") (pintype "passive"))
      (node (ref "C328") (pin "2") (pinfunction "2_2") (pintype "passive"))
      (node (ref "L49") (pin "2") (pinfunction "2_2") (pintype "passive"))
      (node (ref "R109") (pin "1") (pinfunction "1_1") (pintype "passive"))
    )
    (net (code "56") (name "Net-(C329-Pad2)") (class "Default")
      (node (ref "C329") (pin "2") (pinfunction "2_2") (pintype "passive"))
      (node (ref "P10") (pin "1") (pinfunction "1_1") (pintype "passive"))
      (node (ref "R109") (pin "2") (pinfunction "2_2") (pintype "passive"))
    )
    (net (code "57") (name "Net-(U24-XTAL_P)") (class "Default")
      (node (ref "C198") (pin "2") (pinfunction "2_2") (pintype "passive"))
      (node (ref "U24") (pin "54") (pinfunction "XTAL_P_54") (pintype "passive"))
    )
    (net (code "58") (name "P3V3") (class "Default")
      (node (ref "C186") (pin "1") (pinfunction "1_1") (pintype "passive"))
      (node (ref "C187") (pin "1") (pinfunction "1_1") (pintype "passive"))
      (node (ref "C190") (pin "1") (pinfunction "1_1") (pintype "passive"))
      (node (ref "C191") (pin "1") (pinfunction "1_1") (pintype "passive"))
      (node (ref "C192") (pin "1") (pinfunction "1_1") (pintype "passive"))
      (node (ref "C193") (pin "1") (pinfunction "1_1") (pintype "passive"))
      (node (ref "C194") (pin "1") (pinfunction "1_1") (pintype "passive"))
      (node (ref "C195") (pin "1") (pinfunction "1_1") (pintype "passive"))
      (node (ref "L3") (pin "1") (pinfunction "1_1") (pintype "passive"))
      (node (ref "R122") (pin "2") (pinfunction "2_2") (pintype "passive"))
      (node (ref "R123") (pin "2") (pinfunction "2_2") (pintype "passive"))
      (node (ref "R135") (pin "2") (pinfunction "2_2") (pintype "passive"))
      (node (ref "R136") (pin "2") (pinfunction "2_2") (pintype "passive"))
      (node (ref "R137") (pin "2") (pinfunction "2_2") (pintype "passive"))
      (node (ref "R138") (pin "2") (pinfunction "2_2") (pintype "passive"))
      (node (ref "U19") (pin "1") (pinfunction "VDD_1") (pintype "power_in"))
      (node (ref "U24") (pin "20") (pinfunction "VDD3P3_RTC_20") (pintype "passive"))
      (node (ref "U24") (pin "46") (pinfunction "VDD3P3_CPU_46") (pintype "passive"))
      (node (ref "U24") (pin "55") (pinfunction "VDDA1_55") (pintype "power_in"))
      (node (ref "U24") (pin "56") (pinfunction "VDDA2_56") (pintype "passive"))
    )
    (net (code "59") (name "P3V3_VDD3P3_TX") (class "Default")
      (node (ref "C185") (pin "1") (pinfunction "1_1") (pintype "passive"))
      (node (ref "L3") (pin "2") (pinfunction "2_2") (pintype "passive"))
      (node (ref "U24") (pin "2") (pinfunction "VDD3P3_2") (pintype "passive"))
      (node (ref "U24") (pin "3") (pinfunction "VDD3P3_3") (pintype "passive"))
    )
    (net (code "60") (name "SPI5_MISO") (class "Default")
      (node (ref "U24") (pin "10") (pinfunction "GPIO5_10") (pintype "passive"))
    )
    (net (code "61") (name "SPI5_MOSI") (class "Default")
      (node (ref "U24") (pin "11") (pinfunction "GPIO6_11") (pintype "passive"))
    )
    (net (code "62") (name "SPI5_SCK") (class "Default")
      (node (ref "U24") (pin "9") (pinfunction "GPIO4_9") (pintype "passive"))
    )
    (net (code "63") (name "UART4_RX") (class "Default")
      (node (ref "R143") (pin "1") (pinfunction "1_1") (pintype "passive"))
    )
    (net (code "64") (name "UART4_TX") (class "Default")
      (node (ref "R127") (pin "1") (pinfunction "1_1") (pintype "passive"))
    )
    (net (code "65") (name "VDD_TX_SPI") (class "Default")
      (node (ref "C188") (pin "1") (pinfunction "1_1") (pintype "passive"))
      (node (ref "C189") (pin "1") (pinfunction "1_1") (pintype "passive"))
      (node (ref "U24") (pin "29") (pinfunction "VDD_SPI_29") (pintype "passive"))
      (node (ref "U25") (pin "8") (pinfunction "VCC_8") (pintype "passive"))
    )
    (net (code "66") (name "unconnected-(U19-DOUT-Pad2)") (class "Default")
      (node (ref "U19") (pin "2") (pinfunction "DOUT_2") (pintype "output"))
    )
    (net (code "67") (name "unconnected-(U24-GPIO18-Pad24)") (class "Default")
      (node (ref "U24") (pin "24") (pinfunction "GPIO18_24") (pintype "passive"))
    )
    (net (code "68") (name "unconnected-(U24-GPIO37-Pad42)") (class "Default")
      (node (ref "U24") (pin "42") (pinfunction "GPIO37_42") (pintype "passive"))
    )
    (net (code "69") (name "unconnected-(U24-SPICS1-Pad28)") (class "Default")
      (node (ref "U24") (pin "28") (pinfunction "SPICS1_28") (pintype "passive+no_connect"))
    )
    (net (code "70") (name "unconnected-(U24-XTAL_N-Pad53)") (class "Default")
      (node (ref "U24") (pin "53") (pinfunction "XTAL_N_53") (pintype "passive+no_connect"))
    )
  )
)
